# SCH_anne_sch2_2023-06-27_2.net
KiCad netlist of a schematic drawn in EasyEDA
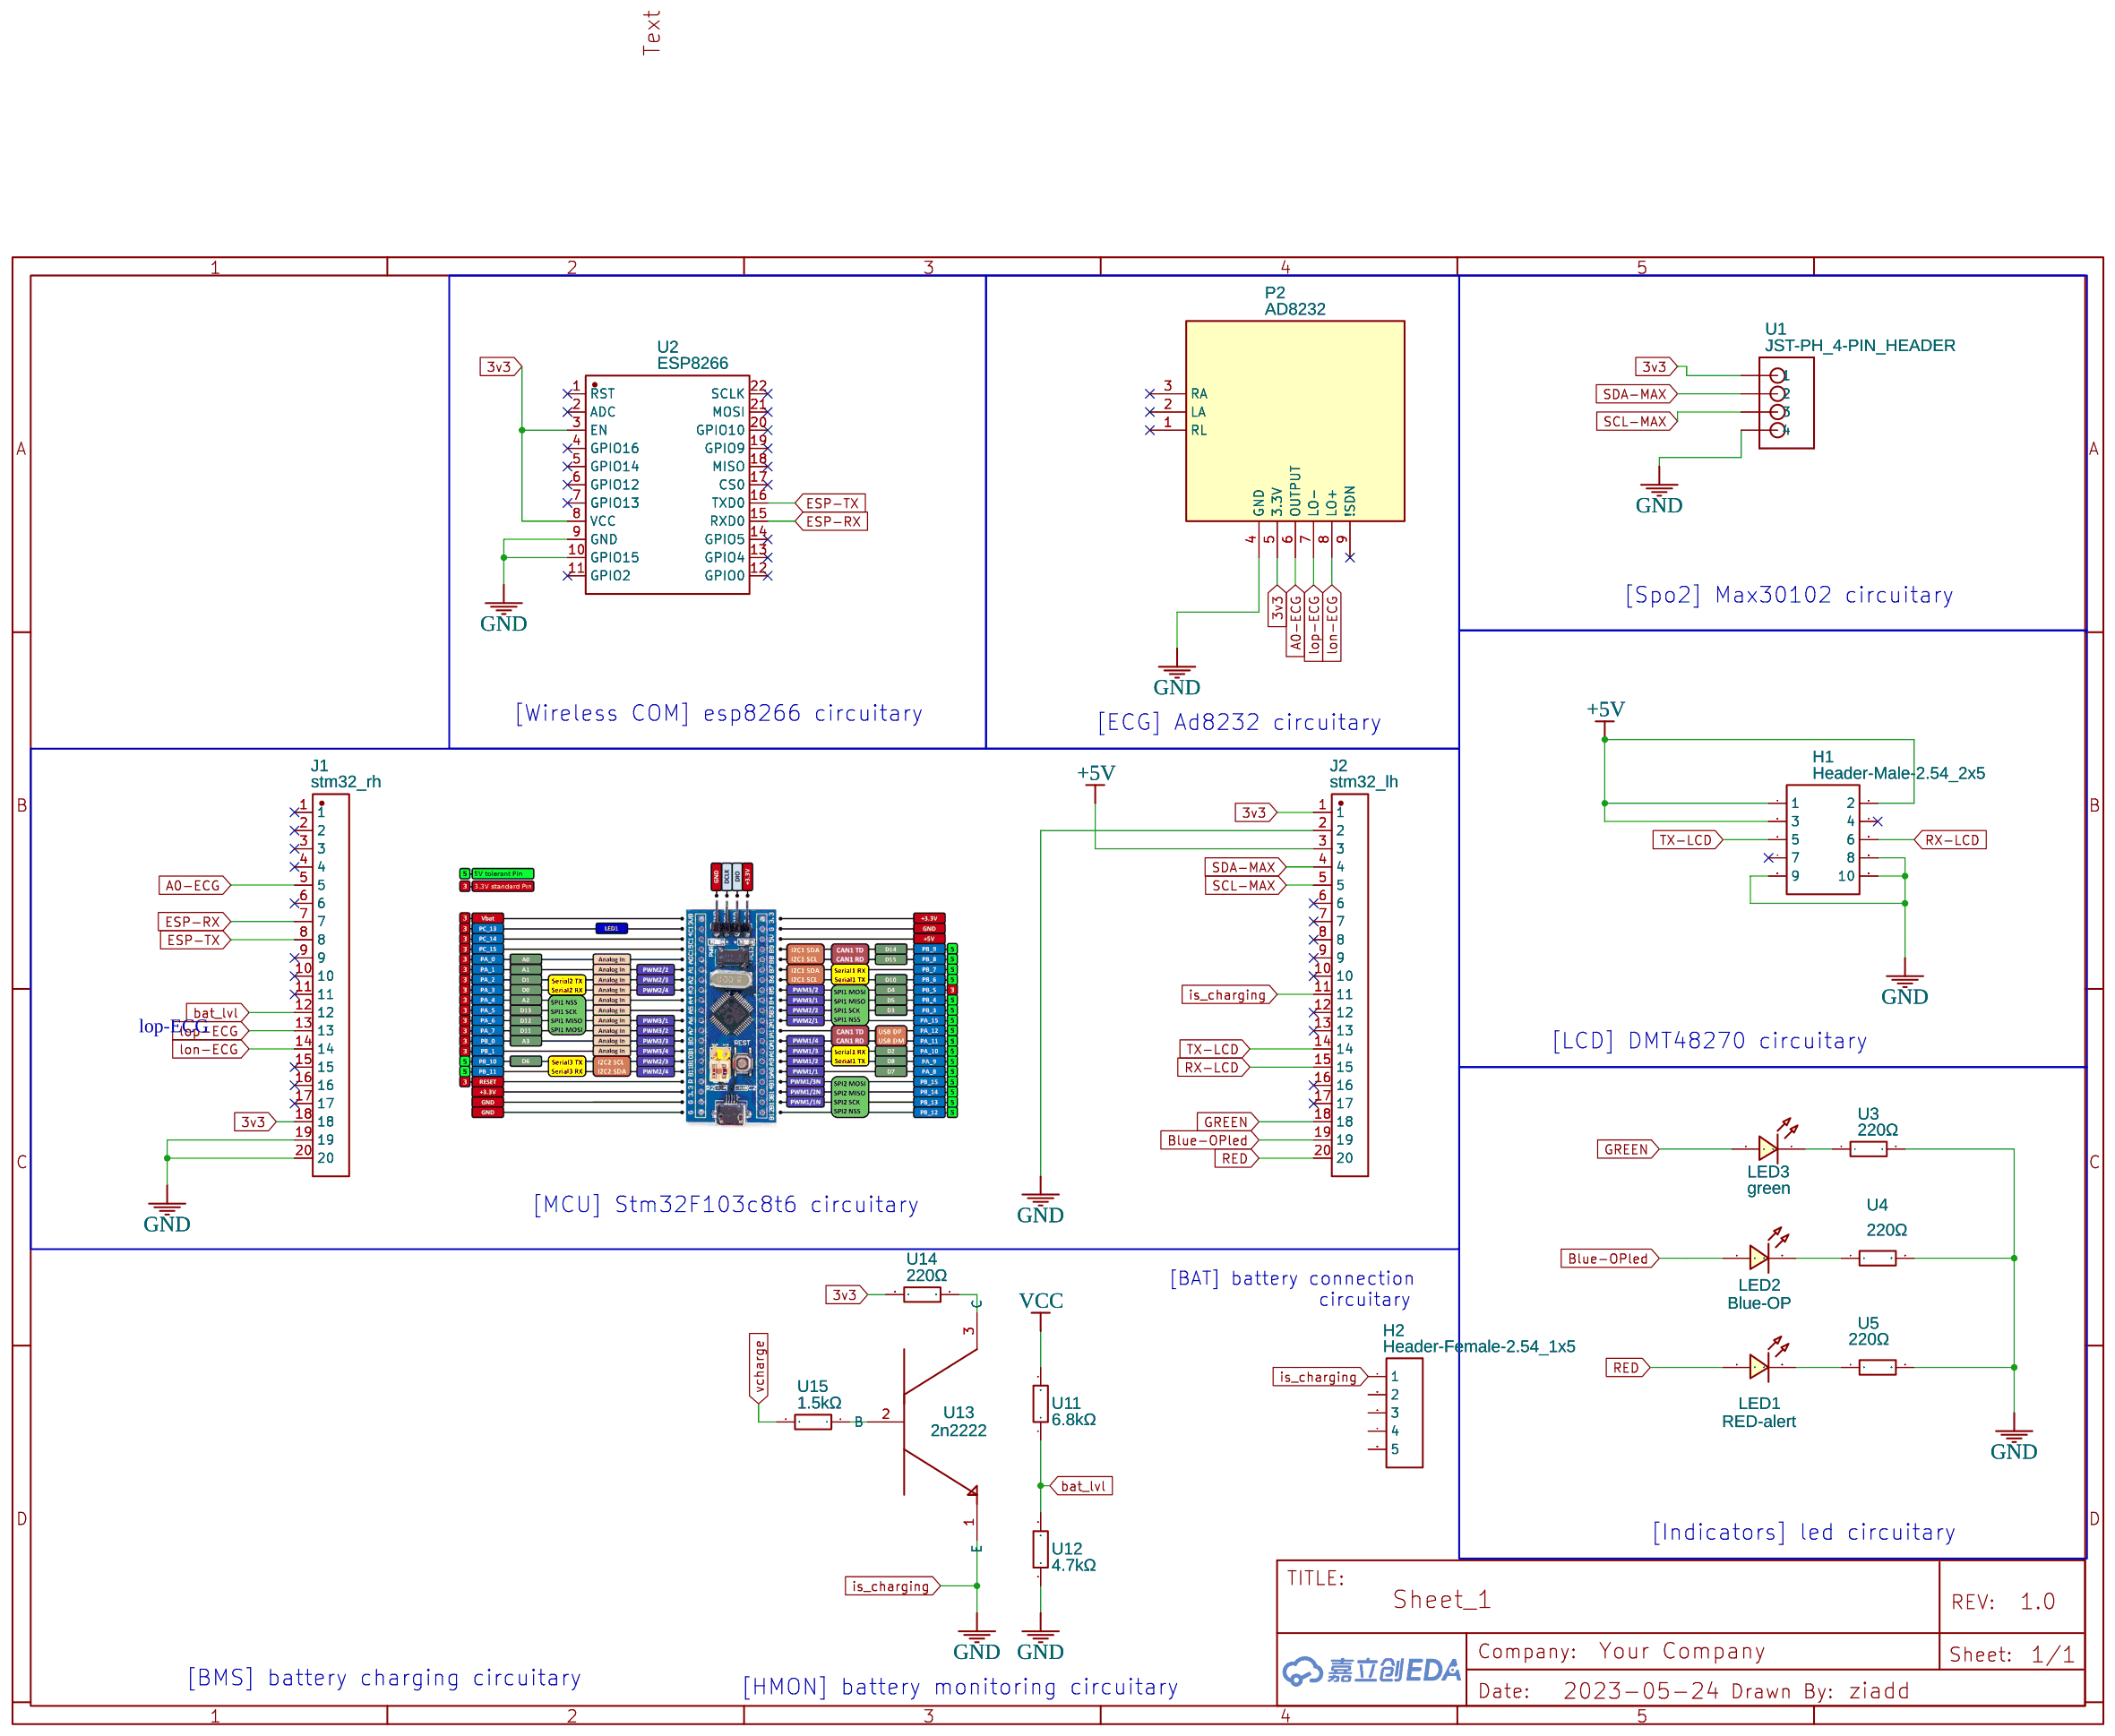
[diagram p0: schematic sheet]

(export (version "E")
  (design (tool "Eeschema 10.0.6"))
  (components
    (comp (ref "H1")
      (value "Header-Male-2.54_2x5")
      (fields
        (field (name "BOM_Manufacturer Part") "2*5pHeaders  Pins 2.54mm")
        (field (name "BOM_Supplier Part") "C28207")
      )
      (libsource (lib "") (part "Header-Male-2.54_2x5"))
    )
    (comp (ref "H2")
      (value "Header-Female-2.54_1x5")
      (fields (field (name "BOM_Manufacturer Part") "2.54-1*5P母") (field (name "BOM_Supplier Part") "C50950"))
      (libsource (lib "") (part "Header-Female-2.54_1x5"))
    )
    (comp (ref "J1")
      (value "stm32_rh")
      (fields
        (field (name "BOM_Manufacturer Part") "2.54-1*20P直针")
        (field (name "BOM_Supplier Part") "C50981")
      )
      (libsource (lib "") (part "Header-Male-2.54_1x20"))
    )
    (comp (ref "J2")
      (value "stm32_lh")
      (fields
        (field (name "BOM_Manufacturer Part") "2.54-1*20P直针")
        (field (name "BOM_Supplier Part") "C50981")
      )
      (libsource (lib "") (part "Header-Male-2.54_1x20"))
    )
    (comp (ref "LED1")
      (value "RED-alert")
      (fields
        (field (name "BOM_Manufacturer Part") "19-217/R6C-AL1M2VY/3T")
        (field (name "BOM_Supplier Part") "C72044")
      )
      (libsource (lib "") (part "LED-0603_R"))
    )
    (comp (ref "LED2")
      (value "Blue-OP")
      (fields
        (field (name "BOM_Manufacturer Part") "19-217/R6C-AL1M2VY/3T")
        (field (name "BOM_Supplier Part") "C72044")
      )
      (libsource (lib "") (part "LED-0603_R"))
    )
    (comp (ref "LED3")
      (value "green")
      (fields
        (field (name "BOM_Manufacturer Part") "19-217/R6C-AL1M2VY/3T")
        (field (name "BOM_Supplier Part") "C72044")
      )
      (libsource (lib "") (part "LED-0603_R"))
    )
    (comp (ref "P2")
      (value "AD8232")
      (fields (field (name "BOM_Supplier Part") "12587"))
      (libsource (lib "") (part "AD8232"))
    )
    (comp (ref "U1") (value "JST-PH_4-PIN_HEADER") (libsource (lib "") (part "JST-PH_4-PIN_HEADER")))
    (comp (ref "U2")
      (value "ESP8266")
      (fields (field (name "BOM_Supplier Part") "C9900003049"))
      (libsource (lib "") (part "ESP8266"))
    )
    (comp (ref "U3")
      (value "220Ω")
      (fields
        (field (name "BOM_Manufacturer Part") "CR1/4W-2K7±5%-ST26")
        (field (name "BOM_Supplier Part") "C2894624")
      )
      (libsource (lib "") (part "CR1/4W-2K7±5%-ST26_2"))
    )
    (comp (ref "U4")
      (value "220Ω")
      (fields
        (field (name "BOM_Manufacturer Part") "CR1/4W-2K7±5%-ST26")
        (field (name "BOM_Supplier Part") "C2894624")
      )
      (libsource (lib "") (part "CR1/4W-2K7±5%-ST26_2"))
    )
    (comp (ref "U5")
      (value "220Ω")
      (fields
        (field (name "BOM_Manufacturer Part") "CR1/4W-2K7±5%-ST26")
        (field (name "BOM_Supplier Part") "C2894624")
      )
      (libsource (lib "") (part "CR1/4W-2K7±5%-ST26_2"))
    )
    (comp (ref "U11")
      (value "6.8kΩ")
      (fields
        (field (name "BOM_Manufacturer Part") "CR1/4W-2K7±5%-ST26")
        (field (name "BOM_Supplier Part") "C2894624")
      )
      (libsource (lib "") (part "CR1/4W-2K7±5%-ST26"))
    )
    (comp (ref "U12")
      (value "4.7kΩ")
      (fields
        (field (name "BOM_Manufacturer Part") "CR1/4W-2K7±5%-ST26")
        (field (name "BOM_Supplier Part") "C2894624")
      )
      (libsource (lib "") (part "CR1/4W-2K7±5%-ST26"))
    )
    (comp (ref "U13") (value "2n2222") (libsource (lib "") (part "2n2222")))
    (comp (ref "U14")
      (value "220Ω")
      (fields
        (field (name "BOM_Manufacturer Part") "CR1/4W-2K7±5%-ST26")
        (field (name "BOM_Supplier Part") "C2894624")
      )
      (libsource (lib "") (part "CR1/4W-2K7±5%-ST26_1"))
    )
    (comp (ref "U15")
      (value "1.5kΩ")
      (fields
        (field (name "BOM_Manufacturer Part") "CR1/4W-2K7±5%-ST26")
        (field (name "BOM_Supplier Part") "C2894624")
      )
      (libsource (lib "") (part "CR1/4W-2K7±5%-ST26_1"))
    )
  )
  (nets
    (net (code "1") (name "+5V") (class "Default")
      (node (ref "H1") (pin "1") (pinfunction "1_1") (pintype "input"))
      (node (ref "H1") (pin "2") (pinfunction "2_2") (pintype "input"))
      (node (ref "H1") (pin "3") (pinfunction "3_3") (pintype "input"))
      (node (ref "J2") (pin "3") (pinfunction "3_3") (pintype "unspecified"))
    )
    (net (code "2") (name "3v3") (class "Default")
      (node (ref "J1") (pin "18") (pinfunction "18_18") (pintype "unspecified"))
      (node (ref "J2") (pin "1") (pinfunction "1_1") (pintype "unspecified"))
      (node (ref "P2") (pin "5") (pinfunction "3.3V_5") (pintype "unspecified"))
      (node (ref "U1") (pin "P1") (pinfunction "1_P1") (pintype "unspecified"))
      (node (ref "U14") (pin "2") (pinfunction "2_2") (pintype "unspecified"))
      (node (ref "U2") (pin "3") (pinfunction "EN_3") (pintype "unspecified"))
      (node (ref "U2") (pin "8") (pinfunction "VCC_8") (pintype "unspecified"))
    )
    (net (code "3") (name "A0-ECG") (class "Default")
      (node (ref "J1") (pin "5") (pinfunction "5_5") (pintype "unspecified"))
      (node (ref "P2") (pin "6") (pinfunction "OUTPUT_6") (pintype "unspecified"))
    )
    (net (code "4") (name "Blue-OPled") (class "Default")
      (node (ref "J2") (pin "19") (pinfunction "19_19") (pintype "unspecified"))
      (node (ref "LED2") (pin "1") (pinfunction "1_1") (pintype "unspecified"))
    )
    (net (code "5") (name "ESP-RX") (class "Default")
      (node (ref "J1") (pin "7") (pinfunction "7_7") (pintype "unspecified"))
      (node (ref "U2") (pin "15") (pinfunction "RXD0_15") (pintype "unspecified"))
    )
    (net (code "6") (name "ESP-TX") (class "Default")
      (node (ref "J1") (pin "8") (pinfunction "8_8") (pintype "unspecified"))
      (node (ref "U2") (pin "16") (pinfunction "TXD0_16") (pintype "unspecified"))
    )
    (net (code "7") (name "GREEN") (class "Default")
      (node (ref "J2") (pin "18") (pinfunction "18_18") (pintype "unspecified"))
      (node (ref "LED3") (pin "1") (pinfunction "1_1") (pintype "unspecified"))
    )
    (net (code "8") (name "Net-(LED1-Pad2)") (class "Default")
      (node (ref "LED1") (pin "2") (pinfunction "2_2") (pintype "unspecified"))
      (node (ref "U5") (pin "1") (pinfunction "1_1") (pintype "unspecified"))
    )
    (net (code "9") (name "Net-(LED2-Pad2)") (class "Default")
      (node (ref "LED2") (pin "2") (pinfunction "2_2") (pintype "unspecified"))
      (node (ref "U4") (pin "1") (pinfunction "1_1") (pintype "unspecified"))
    )
    (net (code "10") (name "Net-(LED3-Pad2)") (class "Default")
      (node (ref "LED3") (pin "2") (pinfunction "2_2") (pintype "unspecified"))
      (node (ref "U3") (pin "1") (pinfunction "1_1") (pintype "unspecified"))
    )
    (net (code "11") (name "RED") (class "Default")
      (node (ref "J2") (pin "20") (pinfunction "20_20") (pintype "unspecified"))
      (node (ref "LED1") (pin "1") (pinfunction "1_1") (pintype "unspecified"))
    )
    (net (code "12") (name "RX-LCD") (class "Default")
      (node (ref "H1") (pin "6") (pinfunction "6_6") (pintype "input"))
      (node (ref "J2") (pin "15") (pinfunction "15_15") (pintype "unspecified"))
    )
    (net (code "13") (name "SCL-MAX") (class "Default")
      (node (ref "J2") (pin "5") (pinfunction "5_5") (pintype "unspecified"))
      (node (ref "U1") (pin "P3") (pinfunction "3_P3") (pintype "unspecified"))
    )
    (net (code "14") (name "SDA-MAX") (class "Default")
      (node (ref "J2") (pin "4") (pinfunction "4_4") (pintype "unspecified"))
      (node (ref "U1") (pin "P2") (pinfunction "2_P2") (pintype "unspecified"))
    )
    (net (code "15") (name "TX-LCD") (class "Default")
      (node (ref "H1") (pin "5") (pinfunction "5_5") (pintype "input"))
      (node (ref "J2") (pin "14") (pinfunction "14_14") (pintype "unspecified"))
    )
    (net (code "16") (name "VCC") (class "Default")
      (node (ref "U11") (pin "2") (pinfunction "2_2") (pintype "unspecified"))
    )
    (net (code "17") (name "bat_lvl") (class "Default")
      (node (ref "J1") (pin "12") (pinfunction "12_12") (pintype "unspecified"))
      (node (ref "U11") (pin "1") (pinfunction "1_1") (pintype "unspecified"))
      (node (ref "U12") (pin "2") (pinfunction "2_2") (pintype "unspecified"))
    )
    (net (code "18") (name "is_charging") (class "Default")
      (node (ref "H1") (pin "10") (pinfunction "10_10") (pintype "input"))
      (node (ref "H1") (pin "8") (pinfunction "8_8") (pintype "input"))
      (node (ref "H1") (pin "9") (pinfunction "9_9") (pintype "input"))
      (node (ref "H2") (pin "1") (pinfunction "1_1") (pintype "input"))
      (node (ref "J1") (pin "19") (pinfunction "19_19") (pintype "unspecified"))
      (node (ref "J1") (pin "20") (pinfunction "20_20") (pintype "unspecified"))
      (node (ref "J2") (pin "11") (pinfunction "11_11") (pintype "unspecified"))
      (node (ref "J2") (pin "2") (pinfunction "2_2") (pintype "unspecified"))
      (node (ref "P2") (pin "4") (pinfunction "GND_4") (pintype "unspecified"))
      (node (ref "U1") (pin "P4") (pinfunction "4_P4") (pintype "unspecified"))
      (node (ref "U12") (pin "1") (pinfunction "1_1") (pintype "unspecified"))
      (node (ref "U2") (pin "10") (pinfunction "GPIO15_10") (pintype "unspecified"))
      (node (ref "U2") (pin "9") (pinfunction "GND_9") (pintype "unspecified"))
      (node (ref "U3") (pin "2") (pinfunction "2_2") (pintype "unspecified"))
      (node (ref "U4") (pin "2") (pinfunction "2_2") (pintype "unspecified"))
      (node (ref "U5") (pin "2") (pinfunction "2_2") (pintype "unspecified"))
    )
    (net (code "19") (name "lon-ECG") (class "Default")
      (node (ref "J1") (pin "14") (pinfunction "14_14") (pintype "unspecified"))
      (node (ref "P2") (pin "8") (pinfunction "LO+_8") (pintype "unspecified"))
    )
    (net (code "20") (name "lop-ECG") (class "Default")
      (node (ref "J1") (pin "13") (pinfunction "13_13") (pintype "unspecified"))
      (node (ref "P2") (pin "7") (pinfunction "LO-_7") (pintype "unspecified"))
    )
    (net (code "21") (name "unconnected-(H1-Pad4)") (class "Default")
      (node (ref "H1") (pin "4") (pinfunction "4_4") (pintype "input+no_connect"))
    )
    (net (code "22") (name "unconnected-(H1-Pad7)") (class "Default")
      (node (ref "H1") (pin "7") (pinfunction "7_7") (pintype "input+no_connect"))
    )
    (net (code "23") (name "unconnected-(H2-Pad2)") (class "Default")
      (node (ref "H2") (pin "2") (pinfunction "2_2") (pintype "input"))
    )
    (net (code "24") (name "unconnected-(H2-Pad3)") (class "Default")
      (node (ref "H2") (pin "3") (pinfunction "3_3") (pintype "input"))
    )
    (net (code "25") (name "unconnected-(H2-Pad4)") (class "Default")
      (node (ref "H2") (pin "4") (pinfunction "4_4") (pintype "input"))
    )
    (net (code "26") (name "unconnected-(H2-Pad5)") (class "Default")
      (node (ref "H2") (pin "5") (pinfunction "5_5") (pintype "input"))
    )
    (net (code "27") (name "unconnected-(J1-Pad1)") (class "Default")
      (node (ref "J1") (pin "1") (pinfunction "1_1") (pintype "unspecified+no_connect"))
    )
    (net (code "28") (name "unconnected-(J1-Pad2)") (class "Default")
      (node (ref "J1") (pin "2") (pinfunction "2_2") (pintype "unspecified+no_connect"))
    )
    (net (code "29") (name "unconnected-(J1-Pad3)") (class "Default")
      (node (ref "J1") (pin "3") (pinfunction "3_3") (pintype "unspecified+no_connect"))
    )
    (net (code "30") (name "unconnected-(J1-Pad4)") (class "Default")
      (node (ref "J1") (pin "4") (pinfunction "4_4") (pintype "unspecified+no_connect"))
    )
    (net (code "31") (name "unconnected-(J1-Pad6)") (class "Default")
      (node (ref "J1") (pin "6") (pinfunction "6_6") (pintype "unspecified+no_connect"))
    )
    (net (code "32") (name "unconnected-(J1-Pad9)") (class "Default")
      (node (ref "J1") (pin "9") (pinfunction "9_9") (pintype "unspecified+no_connect"))
    )
    (net (code "33") (name "unconnected-(J1-Pad10)") (class "Default")
      (node (ref "J1") (pin "10") (pinfunction "10_10") (pintype "unspecified+no_connect"))
    )
    (net (code "34") (name "unconnected-(J1-Pad11)") (class "Default")
      (node (ref "J1") (pin "11") (pinfunction "11_11") (pintype "unspecified+no_connect"))
    )
    (net (code "35") (name "unconnected-(J1-Pad15)") (class "Default")
      (node (ref "J1") (pin "15") (pinfunction "15_15") (pintype "unspecified+no_connect"))
    )
    (net (code "36") (name "unconnected-(J1-Pad16)") (class "Default")
      (node (ref "J1") (pin "16") (pinfunction "16_16") (pintype "unspecified+no_connect"))
    )
    (net (code "37") (name "unconnected-(J1-Pad17)") (class "Default")
      (node (ref "J1") (pin "17") (pinfunction "17_17") (pintype "unspecified+no_connect"))
    )
    (net (code "38") (name "unconnected-(J2-Pad6)") (class "Default")
      (node (ref "J2") (pin "6") (pinfunction "6_6") (pintype "unspecified+no_connect"))
    )
    (net (code "39") (name "unconnected-(J2-Pad7)") (class "Default")
      (node (ref "J2") (pin "7") (pinfunction "7_7") (pintype "unspecified+no_connect"))
    )
    (net (code "40") (name "unconnected-(J2-Pad8)") (class "Default")
      (node (ref "J2") (pin "8") (pinfunction "8_8") (pintype "unspecified+no_connect"))
    )
    (net (code "41") (name "unconnected-(J2-Pad9)") (class "Default")
      (node (ref "J2") (pin "9") (pinfunction "9_9") (pintype "unspecified+no_connect"))
    )
    (net (code "42") (name "unconnected-(J2-Pad10)") (class "Default")
      (node (ref "J2") (pin "10") (pinfunction "10_10") (pintype "unspecified+no_connect"))
    )
    (net (code "43") (name "unconnected-(J2-Pad12)") (class "Default")
      (node (ref "J2") (pin "12") (pinfunction "12_12") (pintype "unspecified+no_connect"))
    )
    (net (code "44") (name "unconnected-(J2-Pad13)") (class "Default")
      (node (ref "J2") (pin "13") (pinfunction "13_13") (pintype "unspecified+no_connect"))
    )
    (net (code "45") (name "unconnected-(J2-Pad16)") (class "Default")
      (node (ref "J2") (pin "16") (pinfunction "16_16") (pintype "unspecified+no_connect"))
    )
    (net (code "46") (name "unconnected-(J2-Pad17)") (class "Default")
      (node (ref "J2") (pin "17") (pinfunction "17_17") (pintype "unspecified+no_connect"))
    )
    (net (code "47") (name "unconnected-(P2-!SDN-Pad9)") (class "Default")
      (node (ref "P2") (pin "9") (pinfunction "!SDN_9") (pintype "unspecified+no_connect"))
    )
    (net (code "48") (name "unconnected-(P2-LA-Pad2)") (class "Default")
      (node (ref "P2") (pin "2") (pinfunction "LA_2") (pintype "unspecified+no_connect"))
    )
    (net (code "49") (name "unconnected-(P2-RA-Pad3)") (class "Default")
      (node (ref "P2") (pin "3") (pinfunction "RA_3") (pintype "unspecified+no_connect"))
    )
    (net (code "50") (name "unconnected-(P2-RL-Pad1)") (class "Default")
      (node (ref "P2") (pin "1") (pinfunction "RL_1") (pintype "unspecified+no_connect"))
    )
    (net (code "51") (name "unconnected-(U2-ADC-Pad2)") (class "Default")
      (node (ref "U2") (pin "2") (pinfunction "ADC_2") (pintype "unspecified+no_connect"))
    )
    (net (code "52") (name "unconnected-(U2-CS0-Pad17)") (class "Default")
      (node (ref "U2") (pin "17") (pinfunction "CS0_17") (pintype "unspecified+no_connect"))
    )
    (net (code "53") (name "unconnected-(U2-GPIO0-Pad12)") (class "Default")
      (node (ref "U2") (pin "12") (pinfunction "GPIO0_12") (pintype "unspecified+no_connect"))
    )
    (net (code "54") (name "unconnected-(U2-GPIO2-Pad11)") (class "Default")
      (node (ref "U2") (pin "11") (pinfunction "GPIO2_11") (pintype "unspecified+no_connect"))
    )
    (net (code "55") (name "unconnected-(U2-GPIO4-Pad13)") (class "Default")
      (node (ref "U2") (pin "13") (pinfunction "GPIO4_13") (pintype "unspecified+no_connect"))
    )
    (net (code "56") (name "unconnected-(U2-GPIO5-Pad14)") (class "Default")
      (node (ref "U2") (pin "14") (pinfunction "GPIO5_14") (pintype "unspecified+no_connect"))
    )
    (net (code "57") (name "unconnected-(U2-GPIO9-Pad19)") (class "Default")
      (node (ref "U2") (pin "19") (pinfunction "GPIO9_19") (pintype "unspecified+no_connect"))
    )
    (net (code "58") (name "unconnected-(U2-GPIO10-Pad20)") (class "Default")
      (node (ref "U2") (pin "20") (pinfunction "GPIO10_20") (pintype "unspecified+no_connect"))
    )
    (net (code "59") (name "unconnected-(U2-GPIO12-Pad6)") (class "Default")
      (node (ref "U2") (pin "6") (pinfunction "GPIO12_6") (pintype "unspecified+no_connect"))
    )
    (net (code "60") (name "unconnected-(U2-GPIO13-Pad7)") (class "Default")
      (node (ref "U2") (pin "7") (pinfunction "GPIO13_7") (pintype "unspecified+no_connect"))
    )
    (net (code "61") (name "unconnected-(U2-GPIO14-Pad5)") (class "Default")
      (node (ref "U2") (pin "5") (pinfunction "GPIO14_5") (pintype "unspecified+no_connect"))
    )
    (net (code "62") (name "unconnected-(U2-GPIO16-Pad4)") (class "Default")
      (node (ref "U2") (pin "4") (pinfunction "GPIO16_4") (pintype "unspecified+no_connect"))
    )
    (net (code "63") (name "unconnected-(U2-MISO-Pad18)") (class "Default")
      (node (ref "U2") (pin "18") (pinfunction "MISO_18") (pintype "unspecified+no_connect"))
    )
    (net (code "64") (name "unconnected-(U2-MOSI-Pad21)") (class "Default")
      (node (ref "U2") (pin "21") (pinfunction "MOSI_21") (pintype "unspecified+no_connect"))
    )
    (net (code "65") (name "unconnected-(U2-RST-Pad1)") (class "Default")
      (node (ref "U2") (pin "1") (pinfunction "RST_1") (pintype "unspecified+no_connect"))
    )
    (net (code "66") (name "unconnected-(U2-SCLK-Pad22)") (class "Default")
      (node (ref "U2") (pin "22") (pinfunction "SCLK_22") (pintype "unspecified+no_connect"))
    )
    (net (code "67") (name "unconnected-(U13-B-Pad2)") (class "Default")
      (node (ref "U13") (pin "2") (pinfunction "B_2") (pintype "unspecified"))
    )
    (net (code "68") (name "unconnected-(U13-C-Pad3)") (class "Default")
      (node (ref "U13") (pin "3") (pinfunction "C_3") (pintype "unspecified"))
    )
    (net (code "69") (name "unconnected-(U13-E-Pad1)") (class "Default")
      (node (ref "U13") (pin "1") (pinfunction "E_1") (pintype "unspecified"))
    )
    (net (code "70") (name "unconnected-(U14-Pad1)") (class "Default")
      (node (ref "U14") (pin "1") (pinfunction "1_1") (pintype "unspecified"))
    )
    (net (code "71") (name "unconnected-(U15-Pad1)") (class "Default")
      (node (ref "U15") (pin "1") (pinfunction "1_1") (pintype "unspecified"))
    )
    (net (code "72") (name "vcharge") (class "Default")
      (node (ref "U15") (pin "2") (pinfunction "2_2") (pintype "unspecified"))
    )
  )
)
